# servo_singal_board.net
KiCad netlist of a schematic drawn in EasyEDA Pro
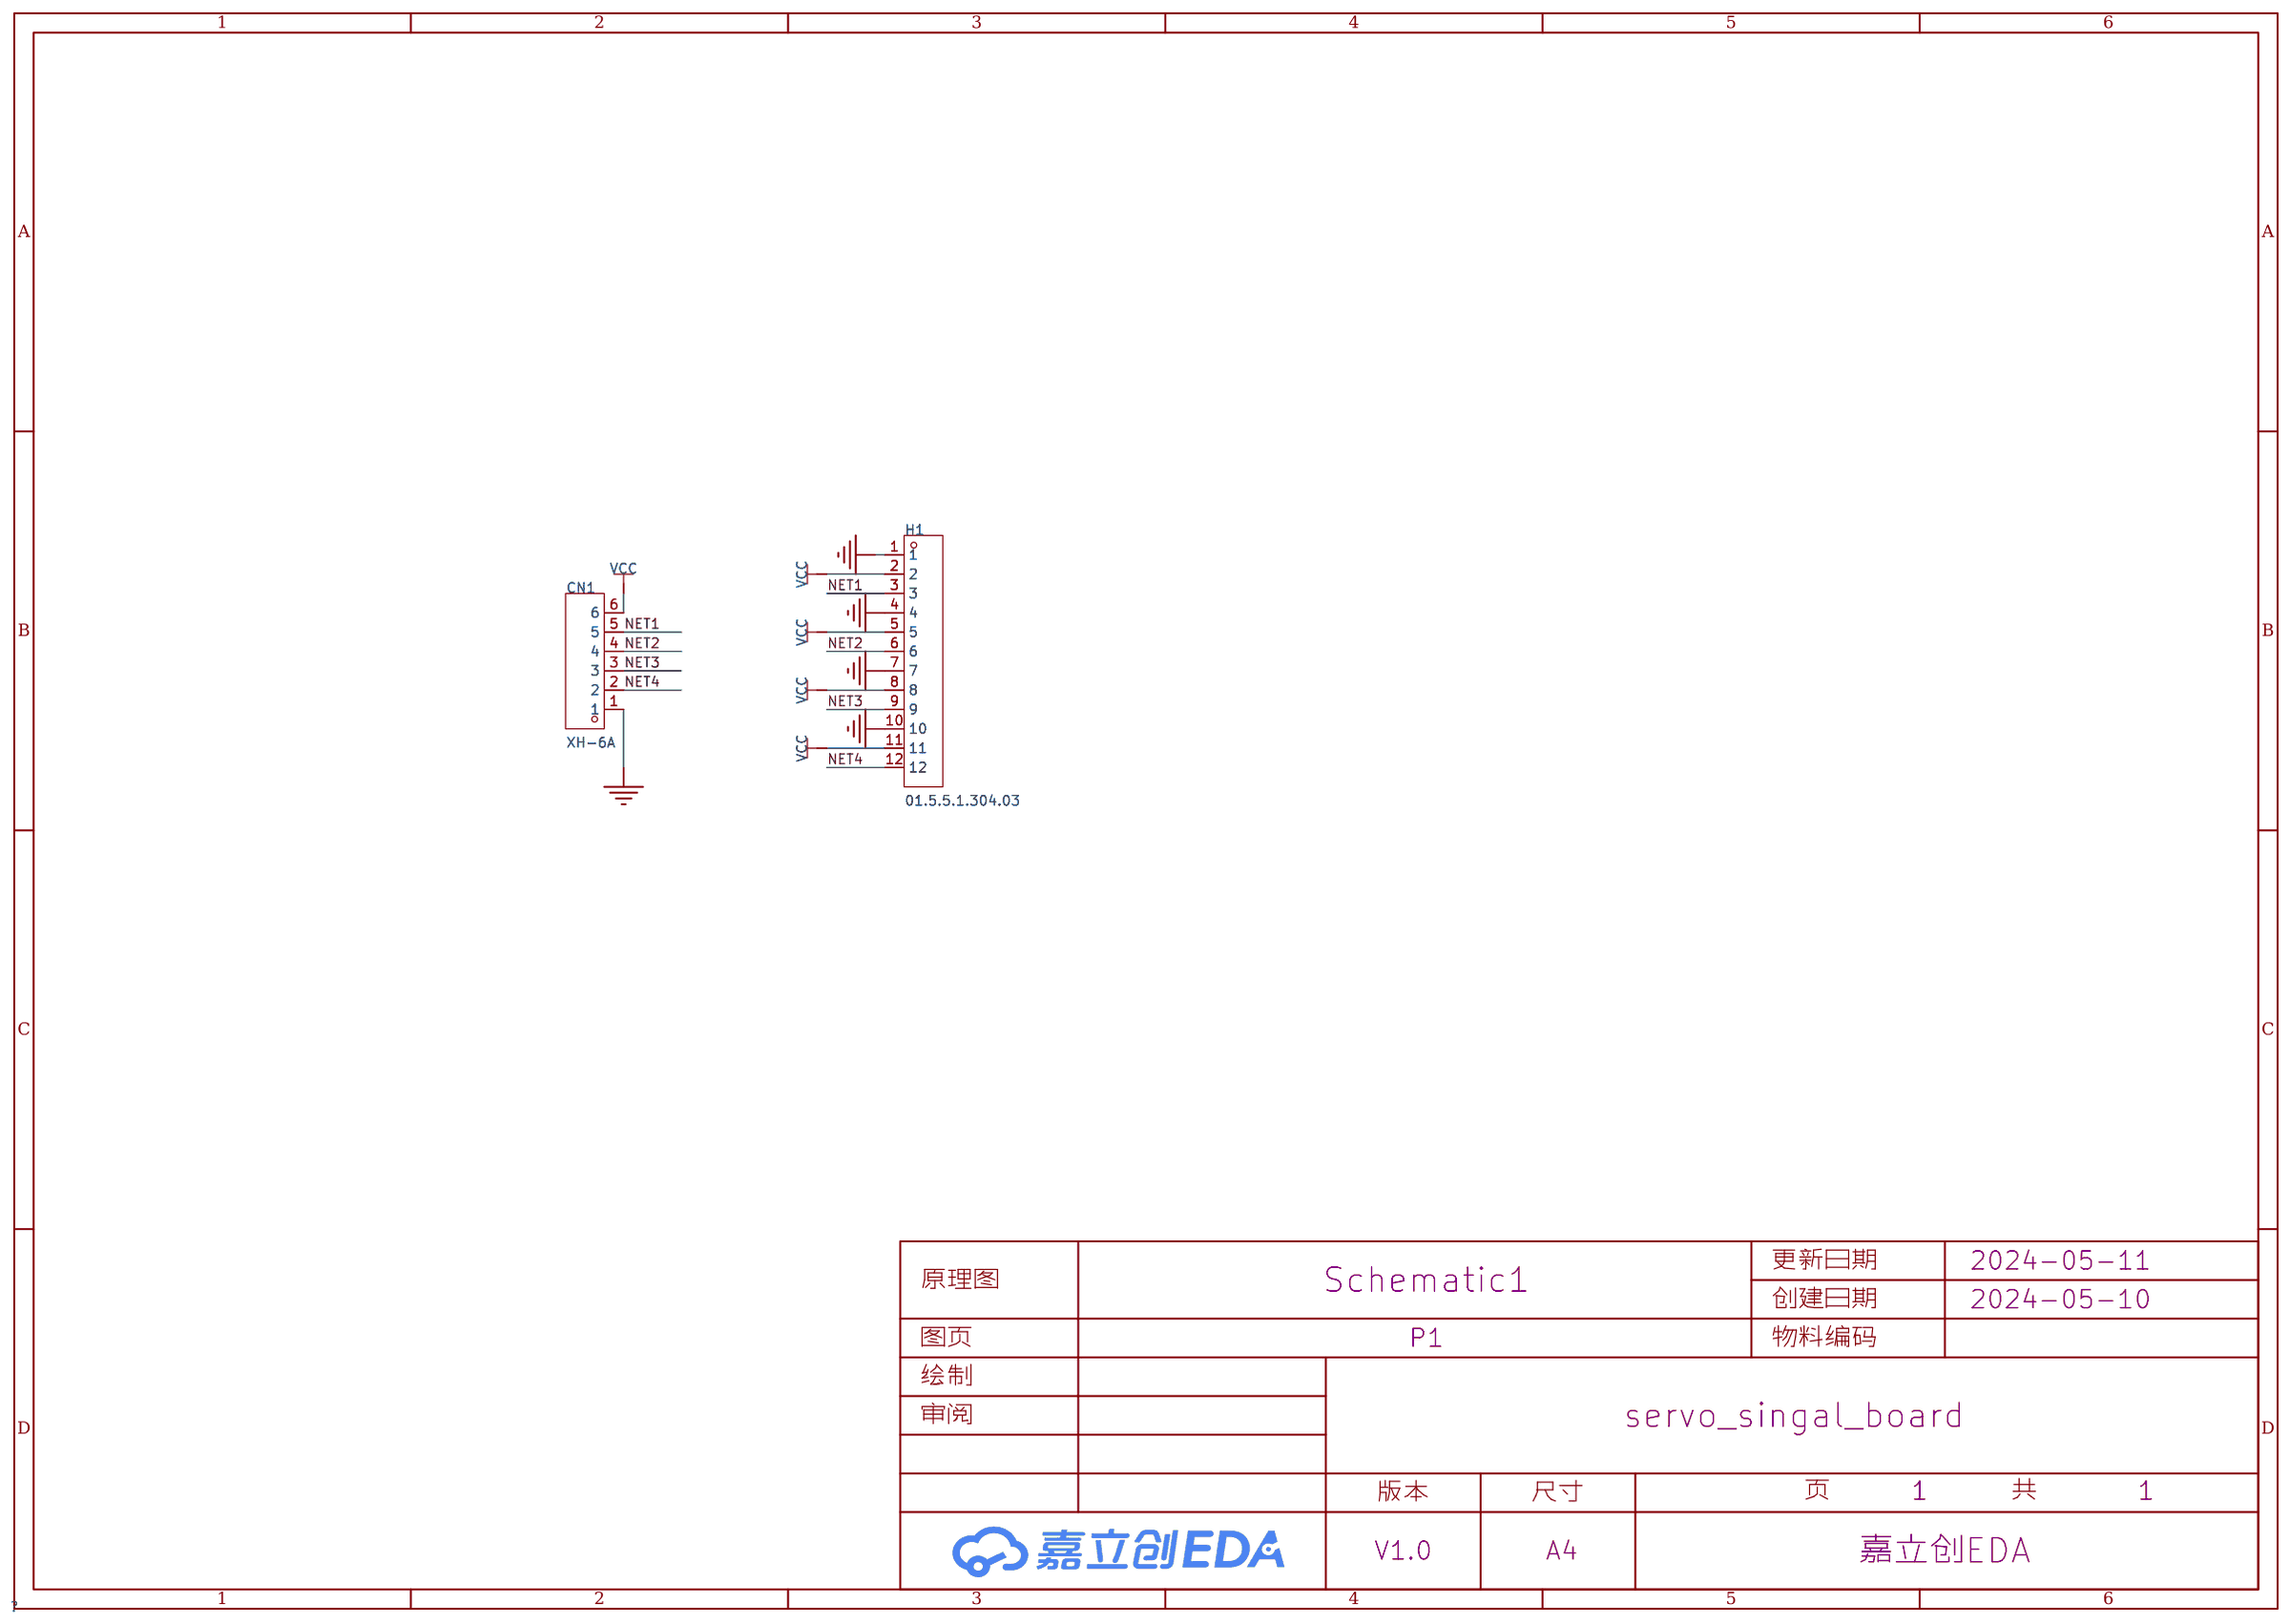
[diagram p0: schematic sheet]

(export (version "E")
  (design (tool "Eeschema 10.0.6"))
  (components
    (comp (ref "CN1")
      (value "XH-6A")
      (footprint "easyedapro:CONN-TH_6P-P2.50_HCTL_XH-6A_C2908604")
      (fields (field (name "Manufacturer") "HCTL(华灿天禄)"))
      (libsource (lib "easyedapro") (part "XH-6A_C2908604"))
    )
    (comp (ref "H1")
      (value "01.5.5.1.304.03")
      (footprint "easyedapro:HDR-TH_12P-P2.54-V-M-R3-C4-S2.54")
      (fields (field (name "Manufacturer") "RealRun(惟赞)"))
      (libsource (lib "easyedapro") (part "01.5.5.1.304.03"))
    )
  )
  (nets
    (net (code "1") (name "/NET1") (class "Default")
      (node (ref "CN1") (pin "5") (pinfunction "5_5") (pintype "unspecified"))
      (node (ref "H1") (pin "3") (pinfunction "3_3") (pintype "unspecified"))
    )
    (net (code "2") (name "/NET2") (class "Default")
      (node (ref "CN1") (pin "4") (pinfunction "4_4") (pintype "unspecified"))
      (node (ref "H1") (pin "6") (pinfunction "6_6") (pintype "unspecified"))
    )
    (net (code "3") (name "/NET3") (class "Default")
      (node (ref "CN1") (pin "3") (pinfunction "3_3") (pintype "unspecified"))
      (node (ref "H1") (pin "9") (pinfunction "9_9") (pintype "unspecified"))
    )
    (net (code "4") (name "/NET4") (class "Default")
      (node (ref "CN1") (pin "2") (pinfunction "2_2") (pintype "unspecified"))
      (node (ref "H1") (pin "12") (pinfunction "12_12") (pintype "unspecified"))
    )
    (net (code "5") (name "GND") (class "Default")
      (node (ref "CN1") (pin "1") (pinfunction "1_1") (pintype "unspecified"))
      (node (ref "H1") (pin "1") (pinfunction "1_1") (pintype "unspecified"))
      (node (ref "H1") (pin "10") (pinfunction "10_10") (pintype "unspecified"))
      (node (ref "H1") (pin "4") (pinfunction "4_4") (pintype "unspecified"))
      (node (ref "H1") (pin "7") (pinfunction "7_7") (pintype "unspecified"))
    )
    (net (code "6") (name "VCC") (class "Default")
      (node (ref "CN1") (pin "6") (pinfunction "6_6") (pintype "unspecified"))
      (node (ref "H1") (pin "11") (pinfunction "11_11") (pintype "unspecified"))
      (node (ref "H1") (pin "2") (pinfunction "2_2") (pintype "unspecified"))
      (node (ref "H1") (pin "5") (pinfunction "5_5") (pintype "unspecified"))
      (node (ref "H1") (pin "8") (pinfunction "8_8") (pintype "unspecified"))
    )
  )
)
